# p1.net
KiCad netlist of a schematic drawn in Altium Designer
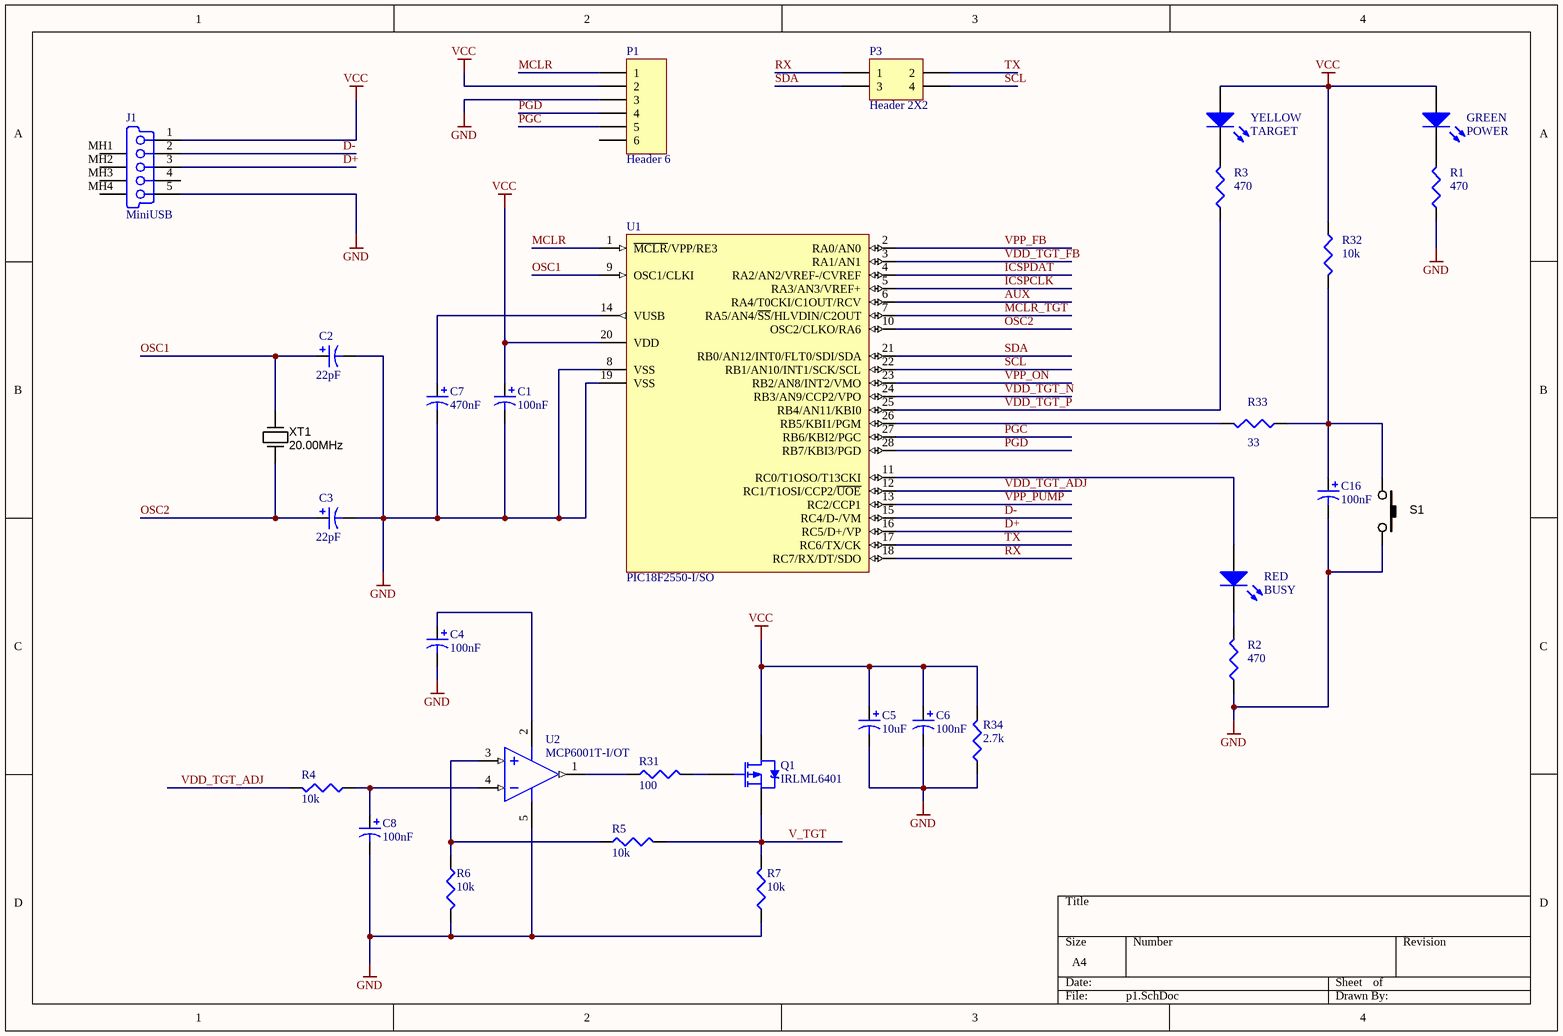
[diagram p0: p1.SchDoc]

(export (version "E")
  (design (tool "Eeschema 10.0.6"))
  (components
    (comp (ref "C1")
      (value "100nF")
      (footprint "C0805")
      (description "Polarized Capacitor (Surface Mount)")
      (fields (field (name "Comment") "Cap Pol3") (field (name "PUBLISHER") "Altium Limited"))
      (libsource (lib "Miscellaneous Devices") (part "Cap Pol3"))
    )
    (comp (ref "C2")
      (value "22pF")
      (footprint "C0805")
      (description "Polarized Capacitor (Surface Mount)")
      (fields (field (name "Comment") "Cap Pol3") (field (name "PUBLISHER") "Altium Limited"))
      (libsource (lib "Miscellaneous Devices") (part "Cap Pol3"))
    )
    (comp (ref "C3")
      (value "22pF")
      (footprint "C0805")
      (description "Polarized Capacitor (Surface Mount)")
      (fields (field (name "Comment") "Cap Pol3") (field (name "PUBLISHER") "Altium Limited"))
      (libsource (lib "Miscellaneous Devices") (part "Cap Pol3"))
    )
    (comp (ref "C4")
      (value "100nF")
      (footprint "C0805")
      (description "Polarized Capacitor (Surface Mount)")
      (fields (field (name "Comment") "Cap Pol3") (field (name "PUBLISHER") "Altium Limited"))
      (libsource (lib "Miscellaneous Devices") (part "Cap Pol3"))
    )
    (comp (ref "C5")
      (value "10uF")
      (footprint "C0805")
      (description "Polarized Capacitor (Surface Mount)")
      (fields (field (name "Comment") "Cap Pol3") (field (name "PUBLISHER") "Altium Limited"))
      (libsource (lib "Miscellaneous Devices") (part "Cap Pol3"))
    )
    (comp (ref "C6")
      (value "100nF")
      (footprint "C0805")
      (description "Polarized Capacitor (Surface Mount)")
      (fields (field (name "Comment") "Cap Pol3") (field (name "PUBLISHER") "Altium Limited"))
      (libsource (lib "Miscellaneous Devices") (part "Cap Pol3"))
    )
    (comp (ref "C7")
      (value "470nF")
      (footprint "C0805")
      (description "Polarized Capacitor (Surface Mount)")
      (fields (field (name "Comment") "Cap Pol3") (field (name "PUBLISHER") "Altium Limited"))
      (libsource (lib "Miscellaneous Devices") (part "Cap Pol3"))
    )
    (comp (ref "C8")
      (value "100nF")
      (footprint "C0805")
      (description "Polarized Capacitor (Surface Mount)")
      (fields (field (name "Comment") "Cap Pol3") (field (name "PUBLISHER") "Altium Limited"))
      (libsource (lib "Miscellaneous Devices") (part "Cap Pol3"))
    )
    (comp (ref "C16")
      (value "100nF")
      (footprint "C0805")
      (description "Polarized Capacitor (Surface Mount)")
      (fields (field (name "Comment") "Cap Pol3") (field (name "PUBLISHER") "Altium Limited"))
      (libsource (lib "Miscellaneous Devices") (part "Cap Pol3"))
    )
    (comp (ref "GREEN")
      (value "POWER")
      (footprint "3.5X2.8X1.9")
      (description "Typical BLUE SiC LED")
      (fields (field (name "PUBLISHER") "Altium Limited"))
      (libsource (lib "Miscellaneous Devices") (part "LED3"))
    )
    (comp (ref "J1")
      (value "MiniUSB")
      (footprint "microusb")
      (fields (field (name "PUBLISHER") "Altium Limited"))
      (libsource (lib "pickit") (part "MicroUSB"))
    )
    (comp (ref "P1")
      (value "Header 6")
      (footprint "HDR1X6")
      (description "Header, 6-Pin")
      (fields (field (name "PUBLISHER") "Altium Limited"))
      (libsource (lib "Miscellaneous Connectors") (part "Header 6"))
    )
    (comp (ref "P3")
      (value "Header 2X2")
      (footprint "HDR2X2")
      (description "Header, 2-Pin, Dual row")
      (fields (field (name "PUBLISHER") "Altium Limited"))
      (libsource (lib "Miscellaneous Connectors") (part "Header 2X2"))
    )
    (comp (ref "Q1")
      (value "IRLML6401")
      (footprint "Micro3_N")
      (description "HEXFET Power MOSFET")
      (fields (field (name "PUBLISHER") "Altium Limited"))
      (libsource (lib "IR Discrete MOSFET - Power") (part "IRLML6401"))
    )
    (comp (ref "R1")
      (value "470")
      (footprint "RESC2012X70N")
      (description "Resistor")
      (fields (field (name "Comment") "Res3") (field (name "PUBLISHER") "Altium Limited"))
      (libsource (lib "Miscellaneous Devices") (part "Res3"))
    )
    (comp (ref "R2")
      (value "470")
      (footprint "RESC2012X70N")
      (description "Resistor")
      (fields (field (name "Comment") "Res3") (field (name "PUBLISHER") "Altium Limited"))
      (libsource (lib "Miscellaneous Devices") (part "Res3"))
    )
    (comp (ref "R3")
      (value "470")
      (footprint "RESC2012X70N")
      (description "Resistor")
      (fields (field (name "Comment") "Res3") (field (name "PUBLISHER") "Altium Limited"))
      (libsource (lib "Miscellaneous Devices") (part "Res3"))
    )
    (comp (ref "R4")
      (value "10k")
      (footprint "RESC2012X70N")
      (description "Resistor")
      (fields (field (name "Comment") "Res3") (field (name "PUBLISHER") "Altium Limited"))
      (libsource (lib "Miscellaneous Devices") (part "Res3"))
    )
    (comp (ref "R5")
      (value "10k")
      (footprint "RESC2012X70N")
      (description "Resistor")
      (fields (field (name "Comment") "Res3") (field (name "PUBLISHER") "Altium Limited"))
      (libsource (lib "Miscellaneous Devices") (part "Res3"))
    )
    (comp (ref "R6")
      (value "10k")
      (footprint "RESC2012X70N")
      (description "Resistor")
      (fields (field (name "Comment") "Res3") (field (name "PUBLISHER") "Altium Limited"))
      (libsource (lib "Miscellaneous Devices") (part "Res3"))
    )
    (comp (ref "R7")
      (value "10k")
      (footprint "RESC2012X70N")
      (description "Resistor")
      (fields (field (name "Comment") "Res3") (field (name "PUBLISHER") "Altium Limited"))
      (libsource (lib "Miscellaneous Devices") (part "Res3"))
    )
    (comp (ref "R31")
      (value "100")
      (footprint "RESC2012X70N")
      (description "Resistor")
      (fields (field (name "Comment") "Res3") (field (name "PUBLISHER") "Altium Limited"))
      (libsource (lib "Miscellaneous Devices") (part "Res3"))
    )
    (comp (ref "R32")
      (value "10k")
      (footprint "RESC2012X70N")
      (description "Resistor")
      (fields (field (name "Comment") "Res3") (field (name "PUBLISHER") "Altium Limited"))
      (libsource (lib "Miscellaneous Devices") (part "Res3"))
    )
    (comp (ref "R33")
      (value "33")
      (footprint "RESC2012X70N")
      (description "Resistor")
      (fields (field (name "Comment") "Res3") (field (name "PUBLISHER") "Altium Limited"))
      (libsource (lib "Miscellaneous Devices") (part "Res3"))
    )
    (comp (ref "R34")
      (value "2.7k")
      (footprint "RESC2012X70N")
      (description "Resistor")
      (fields (field (name "Comment") "Res3") (field (name "PUBLISHER") "Altium Limited"))
      (libsource (lib "Miscellaneous Devices") (part "Res3"))
    )
    (comp (ref "RED")
      (value "BUSY")
      (footprint "3.5X2.8X1.9")
      (description "Typical BLUE SiC LED")
      (fields (field (name "PUBLISHER") "Altium Limited"))
      (libsource (lib "Miscellaneous Devices") (part "LED3"))
    )
    (comp (ref "S1")
      (value "TS-1143S-WP")
      (footprint "TS-1143S")
      (description "Switch SMD Tact 4.3mm Stem")
      (libsource (lib "PBL - Switches") (part "SW_SMD_PB_4.3mm"))
    )
    (comp (ref "U1")
      (value "PIC18F2550-I/SO")
      (footprint "SOIC-SO28_N")
      (fields (field (name "PUBLISHER") "Altium Limited"))
      (libsource (lib "Microchip Microcontroller 8-Bit PIC18") (part "PIC18F2550-I/SO"))
    )
    (comp (ref "U2")
      (value "MCP6001T-I/OT")
      (footprint "SOT-23-OT5_N")
      (description "1 MHz, Low-Power Operational Amplifier, 5-Pin SOT-23, Industrial Temperature, Tape and Reel")
      (fields (field (name "PUBLISHER") "Altium Limited"))
      (libsource (lib "Microchip Linear Devices") (part "MCP6001T-I/OT"))
    )
    (comp (ref "XT1")
      (value "20.00MHz")
      (footprint "CRYSTAL_HC49-US-SM")
      (description "Resonator Ceramic 20.00 MHz 30ppm")
      (libsource (lib "PBL - Resonators") (part "Crystal_6MHz_HC49/US"))
    )
    (comp (ref "YELLOW")
      (value "TARGET")
      (footprint "3.5X2.8X1.9")
      (description "Typical BLUE SiC LED")
      (fields (field (name "PUBLISHER") "Altium Limited"))
      (libsource (lib "Miscellaneous Devices") (part "LED3"))
    )
  )
  (nets
    (net (code "1") (name "/AUX") (class "Default")
      (node (ref "U1") (pin "6") (pinfunction "RA4/T0CKI/C1OUT/RCV_6") (pintype "bidirectional"))
    )
    (net (code "2") (name "/D+") (class "Default")
      (node (ref "J1") (pin "3") (pinfunction "D+_3") (pintype "passive"))
      (node (ref "U1") (pin "16") (pinfunction "RC5/D+/VP_16") (pintype "bidirectional"))
    )
    (net (code "3") (name "/D-") (class "Default")
      (node (ref "J1") (pin "2") (pinfunction "D-_2") (pintype "passive"))
      (node (ref "U1") (pin "15") (pinfunction "RC4/D-/VM_15") (pintype "bidirectional"))
    )
    (net (code "4") (name "/ICSPCLK") (class "Default")
      (node (ref "U1") (pin "5") (pinfunction "RA3/AN3/VREF+_5") (pintype "bidirectional"))
    )
    (net (code "5") (name "/ICSPDAT") (class "Default")
      (node (ref "U1") (pin "4") (pinfunction "RA2/AN2/VREF-/CVREF_4") (pintype "bidirectional"))
    )
    (net (code "6") (name "/MCLR") (class "Default")
      (node (ref "P1") (pin "1") (pinfunction "1_1") (pintype "passive"))
      (node (ref "U1") (pin "1") (pinfunction "~{MCLR}/VPP/RE3_1") (pintype "input"))
    )
    (net (code "7") (name "/MCLR_TGT") (class "Default")
      (node (ref "U1") (pin "7") (pinfunction "RA5/AN4/~{SS}/HLVDIN/C2OUT_7") (pintype "bidirectional"))
    )
    (net (code "8") (name "/OSC1") (class "Default")
      (node (ref "C2") (pin "1") (pinfunction "1_1") (pintype "passive"))
      (node (ref "U1") (pin "9") (pinfunction "OSC1/CLKI_9") (pintype "input"))
      (node (ref "XT1") (pin "2") (pinfunction "OUT_2") (pintype "passive"))
    )
    (net (code "9") (name "/OSC2") (class "Default")
      (node (ref "C3") (pin "1") (pinfunction "1_1") (pintype "passive"))
      (node (ref "U1") (pin "10") (pinfunction "OSC2/CLKO/RA6_10") (pintype "bidirectional"))
      (node (ref "XT1") (pin "1") (pinfunction "IN_1") (pintype "passive"))
    )
    (net (code "10") (name "/PGC") (class "Default")
      (node (ref "P1") (pin "5") (pinfunction "5_5") (pintype "passive"))
      (node (ref "U1") (pin "27") (pinfunction "RB6/KBI2/PGC_27") (pintype "bidirectional"))
    )
    (net (code "11") (name "/PGD") (class "Default")
      (node (ref "P1") (pin "4") (pinfunction "4_4") (pintype "passive"))
      (node (ref "U1") (pin "28") (pinfunction "RB7/KBI3/PGD_28") (pintype "bidirectional"))
    )
    (net (code "12") (name "/RX") (class "Default")
      (node (ref "P3") (pin "1") (pinfunction "1_1") (pintype "passive"))
      (node (ref "U1") (pin "18") (pinfunction "RC7/RX/DT/SDO_18") (pintype "bidirectional"))
    )
    (net (code "13") (name "/SCL") (class "Default")
      (node (ref "P3") (pin "4") (pinfunction "4_4") (pintype "passive"))
      (node (ref "U1") (pin "22") (pinfunction "RB1/AN10/INT1/SCK/SCL_22") (pintype "bidirectional"))
    )
    (net (code "14") (name "/SDA") (class "Default")
      (node (ref "P3") (pin "3") (pinfunction "3_3") (pintype "passive"))
      (node (ref "U1") (pin "21") (pinfunction "RB0/AN12/INT0/FLT0/SDI/SDA_21") (pintype "bidirectional"))
    )
    (net (code "15") (name "/TX") (class "Default")
      (node (ref "P3") (pin "2") (pinfunction "2_2") (pintype "passive"))
      (node (ref "U1") (pin "17") (pinfunction "RC6/TX/CK_17") (pintype "bidirectional"))
    )
    (net (code "16") (name "/VDD_TGT_ADJ") (class "Default")
      (node (ref "R4") (pin "2") (pinfunction "2_2") (pintype "passive"))
      (node (ref "U1") (pin "12") (pinfunction "RC1/T1OSI/CCP2/~{UOE}_12") (pintype "bidirectional"))
    )
    (net (code "17") (name "/VDD_TGT_FB") (class "Default")
      (node (ref "U1") (pin "3") (pinfunction "RA1/AN1_3") (pintype "bidirectional"))
    )
    (net (code "18") (name "/VDD_TGT_N") (class "Default")
      (node (ref "U1") (pin "24") (pinfunction "RB3/AN9/CCP2/VPO_24") (pintype "bidirectional"))
    )
    (net (code "19") (name "/VDD_TGT_P") (class "Default")
      (node (ref "R3") (pin "1") (pinfunction "1_1") (pintype "passive"))
      (node (ref "U1") (pin "25") (pinfunction "RB4/AN11/KBI0_25") (pintype "bidirectional"))
    )
    (net (code "20") (name "/VPP_FB") (class "Default")
      (node (ref "U1") (pin "2") (pinfunction "RA0/AN0_2") (pintype "bidirectional"))
    )
    (net (code "21") (name "/VPP_ON") (class "Default")
      (node (ref "U1") (pin "23") (pinfunction "RB2/AN8/INT2/VMO_23") (pintype "bidirectional"))
    )
    (net (code "22") (name "/VPP_PUMP") (class "Default")
      (node (ref "U1") (pin "13") (pinfunction "RC2/CCP1_13") (pintype "bidirectional"))
    )
    (net (code "23") (name "/V_TGT") (class "Default")
      (node (ref "Q1") (pin "2") (pinfunction "S_2") (pintype "passive"))
      (node (ref "R5") (pin "2") (pinfunction "2_2") (pintype "passive"))
      (node (ref "R7") (pin "2") (pinfunction "2_2") (pintype "passive"))
    )
    (net (code "24") (name "GND") (class "Default")
      (node (ref "C1") (pin "2") (pinfunction "2_2") (pintype "passive"))
      (node (ref "C16") (pin "2") (pinfunction "2_2") (pintype "passive"))
      (node (ref "C2") (pin "2") (pinfunction "2_2") (pintype "passive"))
      (node (ref "C3") (pin "2") (pinfunction "2_2") (pintype "passive"))
      (node (ref "C4") (pin "2") (pinfunction "2_2") (pintype "passive"))
      (node (ref "C5") (pin "2") (pinfunction "2_2") (pintype "passive"))
      (node (ref "C6") (pin "2") (pinfunction "2_2") (pintype "passive"))
      (node (ref "C7") (pin "2") (pinfunction "2_2") (pintype "passive"))
      (node (ref "C8") (pin "2") (pinfunction "2_2") (pintype "passive"))
      (node (ref "J1") (pin "5") (pinfunction "GND_5") (pintype "passive"))
      (node (ref "P1") (pin "3") (pinfunction "3_3") (pintype "passive"))
      (node (ref "R1") (pin "1") (pinfunction "1_1") (pintype "passive"))
      (node (ref "R2") (pin "1") (pinfunction "1_1") (pintype "passive"))
      (node (ref "R34") (pin "1") (pinfunction "1_1") (pintype "passive"))
      (node (ref "R6") (pin "2") (pinfunction "2_2") (pintype "passive"))
      (node (ref "R7") (pin "1") (pinfunction "1_1") (pintype "passive"))
      (node (ref "S1") (pin "2") (pintype "passive"))
      (node (ref "U1") (pin "19") (pinfunction "VSS_19") (pintype "power_in"))
      (node (ref "U1") (pin "8") (pinfunction "VSS_8") (pintype "power_in"))
      (node (ref "U2") (pin "5") (pinfunction "VDD_5") (pintype "power_in"))
    )
    (net (code "25") (name "Net-(C16-Pad1)") (class "Default")
      (node (ref "C16") (pin "1") (pinfunction "1_1") (pintype "passive"))
      (node (ref "R32") (pin "2") (pinfunction "2_2") (pintype "passive"))
      (node (ref "R33") (pin "1") (pinfunction "1_1") (pintype "passive"))
      (node (ref "S1") (pin "1") (pintype "passive"))
    )
    (net (code "26") (name "Net-(GREEN-K)") (class "Default")
      (node (ref "GREEN") (pin "2") (pinfunction "K_2") (pintype "passive"))
      (node (ref "R1") (pin "2") (pinfunction "2_2") (pintype "passive"))
    )
    (net (code "27") (name "Net-(Q1-G)") (class "Default")
      (node (ref "Q1") (pin "1") (pinfunction "G_1") (pintype "passive"))
      (node (ref "R31") (pin "2") (pinfunction "2_2") (pintype "passive"))
    )
    (net (code "28") (name "Net-(RED-A)") (class "Default")
      (node (ref "RED") (pin "1") (pinfunction "A_1") (pintype "passive"))
      (node (ref "U1") (pin "11") (pinfunction "RC0/T1OSO/T13CKI_11") (pintype "bidirectional"))
    )
    (net (code "29") (name "Net-(RED-K)") (class "Default")
      (node (ref "R2") (pin "2") (pinfunction "2_2") (pintype "passive"))
      (node (ref "RED") (pin "2") (pinfunction "K_2") (pintype "passive"))
    )
    (net (code "30") (name "Net-(U1-RB5{slash}KBI1{slash}PGM)") (class "Default")
      (node (ref "R33") (pin "2") (pinfunction "2_2") (pintype "passive"))
      (node (ref "U1") (pin "26") (pinfunction "RB5/KBI1/PGM_26") (pintype "bidirectional"))
    )
    (net (code "31") (name "Net-(U1-VUSB)") (class "Default")
      (node (ref "C7") (pin "1") (pinfunction "1_1") (pintype "passive"))
      (node (ref "U1") (pin "14") (pinfunction "VUSB_14") (pintype "output"))
    )
    (net (code "32") (name "Net-(U2-VIN+)") (class "Default")
      (node (ref "R5") (pin "1") (pinfunction "1_1") (pintype "passive"))
      (node (ref "R6") (pin "1") (pinfunction "1_1") (pintype "passive"))
      (node (ref "U2") (pin "3") (pinfunction "VIN+_3") (pintype "input"))
    )
    (net (code "33") (name "Net-(U2-VIN-)") (class "Default")
      (node (ref "C8") (pin "1") (pinfunction "1_1") (pintype "passive"))
      (node (ref "R4") (pin "1") (pinfunction "1_1") (pintype "passive"))
      (node (ref "U2") (pin "4") (pinfunction "VIN-_4") (pintype "input"))
    )
    (net (code "34") (name "Net-(U2-VOUT)") (class "Default")
      (node (ref "R31") (pin "1") (pinfunction "1_1") (pintype "passive"))
      (node (ref "U2") (pin "1") (pinfunction "VOUT_1") (pintype "output"))
    )
    (net (code "35") (name "Net-(U2-VSS)") (class "Default")
      (node (ref "C4") (pin "1") (pinfunction "1_1") (pintype "passive"))
      (node (ref "U2") (pin "2") (pinfunction "VSS_2") (pintype "power_in"))
    )
    (net (code "36") (name "Net-(YELLOW-K)") (class "Default")
      (node (ref "R3") (pin "2") (pinfunction "2_2") (pintype "passive"))
      (node (ref "YELLOW") (pin "2") (pinfunction "K_2") (pintype "passive"))
    )
    (net (code "37") (name "VCC") (class "Default")
      (node (ref "C1") (pin "1") (pinfunction "1_1") (pintype "passive"))
      (node (ref "C5") (pin "1") (pinfunction "1_1") (pintype "passive"))
      (node (ref "C6") (pin "1") (pinfunction "1_1") (pintype "passive"))
      (node (ref "GREEN") (pin "1") (pinfunction "A_1") (pintype "passive"))
      (node (ref "J1") (pin "1") (pinfunction "V_BUS_(5V)_1") (pintype "passive"))
      (node (ref "P1") (pin "2") (pinfunction "2_2") (pintype "passive"))
      (node (ref "Q1") (pin "3") (pinfunction "D_3") (pintype "passive"))
      (node (ref "R32") (pin "1") (pinfunction "1_1") (pintype "passive"))
      (node (ref "R34") (pin "2") (pinfunction "2_2") (pintype "passive"))
      (node (ref "U1") (pin "20") (pinfunction "VDD_20") (pintype "power_in"))
      (node (ref "YELLOW") (pin "1") (pinfunction "A_1") (pintype "passive"))
    )
    (net (code "38") (name "unconnected-(J1-NC-Pad4)") (class "Default")
      (node (ref "J1") (pin "4") (pinfunction "NC_4") (pintype "passive"))
    )
    (net (code "39") (name "unconnected-(J1-Tab-PadMH1)") (class "Default")
      (node (ref "J1") (pin "MH1") (pinfunction "Tab_MH1") (pintype "passive"))
    )
    (net (code "40") (name "unconnected-(J1-Tab-PadMH2)") (class "Default")
      (node (ref "J1") (pin "MH2") (pinfunction "Tab_MH2") (pintype "passive"))
    )
    (net (code "41") (name "unconnected-(J1-Tab-PadMH3)") (class "Default")
      (node (ref "J1") (pin "MH3") (pinfunction "Tab_MH3") (pintype "passive"))
    )
    (net (code "42") (name "unconnected-(J1-Tab-PadMH4)") (class "Default")
      (node (ref "J1") (pin "MH4") (pinfunction "Tab_MH4") (pintype "passive"))
    )
    (net (code "43") (name "unconnected-(P1-Pad6)") (class "Default")
      (node (ref "P1") (pin "6") (pinfunction "6_6") (pintype "passive"))
    )
  )
)
